# Main_PDU.net
KiCad netlist of a schematic drawn in EAGLE
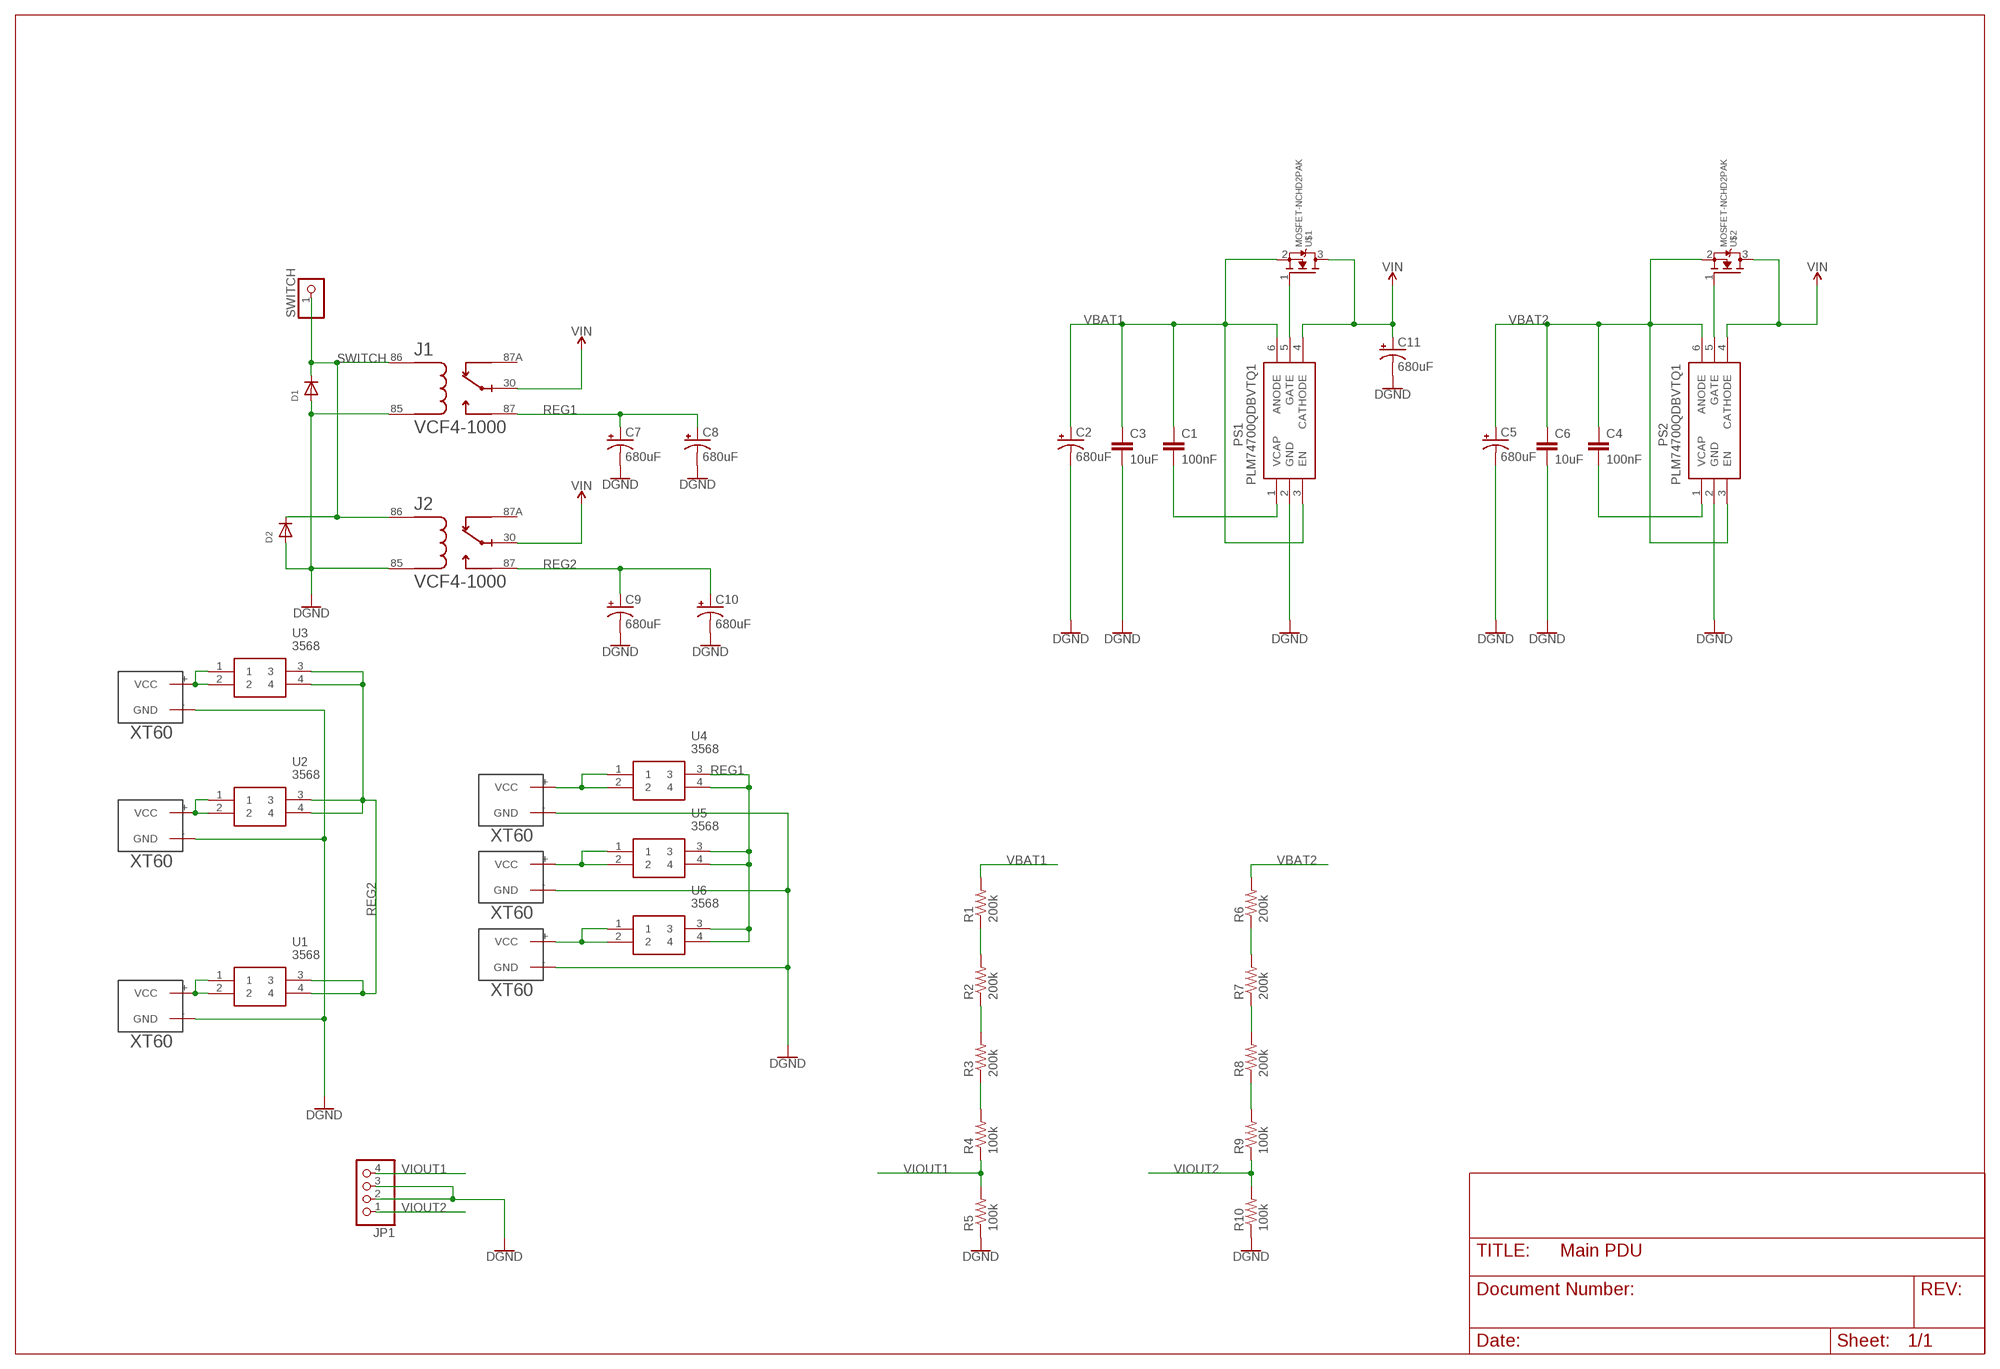
[diagram p0: schematic, sheet 1]

(export (version "E")
  (design (tool "Eeschema 10.0.6"))
  (components
    (comp (ref "C1")
      (value "100nF")
      (footprint "eagle-import:C0805")
      (libsource (lib "eagle-import") (part "C-EUC0805"))
    )
    (comp (ref "C2")
      (value "680uF")
      (footprint "eagle-import:E5-10,5")
      (libsource (lib "eagle-import") (part "CPOL-USE5-10.5"))
    )
    (comp (ref "C3")
      (value "10uF")
      (footprint "eagle-import:C1206")
      (libsource (lib "eagle-import") (part "C-EUC1206"))
    )
    (comp (ref "C4")
      (value "100nF")
      (footprint "eagle-import:C0805")
      (libsource (lib "eagle-import") (part "C-EUC0805"))
    )
    (comp (ref "C5")
      (value "680uF")
      (footprint "eagle-import:E5-10,5")
      (libsource (lib "eagle-import") (part "CPOL-USE5-10.5"))
    )
    (comp (ref "C6")
      (value "10uF")
      (footprint "eagle-import:C1206")
      (libsource (lib "eagle-import") (part "C-EUC1206"))
    )
    (comp (ref "C7")
      (value "680uF")
      (footprint "eagle-import:E5-10,5")
      (libsource (lib "eagle-import") (part "CPOL-USE5-10.5"))
    )
    (comp (ref "C8")
      (value "680uF")
      (footprint "eagle-import:E5-10,5")
      (libsource (lib "eagle-import") (part "CPOL-USE5-10.5"))
    )
    (comp (ref "C9")
      (value "680uF")
      (footprint "eagle-import:E5-10,5")
      (libsource (lib "eagle-import") (part "CPOL-USE5-10.5"))
    )
    (comp (ref "C10")
      (value "680uF")
      (footprint "eagle-import:E5-10,5")
      (libsource (lib "eagle-import") (part "CPOL-USE5-10.5"))
    )
    (comp (ref "C11")
      (value "680uF")
      (footprint "eagle-import:E5-10,5")
      (libsource (lib "eagle-import") (part "CPOL-USE5-10.5"))
    )
    (comp (ref "D1")
      (value "DIODESOD-123")
      (footprint "eagle-import:SOD-123")
      (libsource (lib "eagle-import") (part "DIODESOD-123"))
    )
    (comp (ref "D2")
      (value "DIODESOD-123")
      (footprint "eagle-import:SOD-123")
      (libsource (lib "eagle-import") (part "DIODESOD-123"))
    )
    (comp (ref "J1")
      (value "VCF4-1000")
      (footprint "eagle-import:TE_VCF4-1000")
      (fields (field (name "COMMENT") "1393310-3") (field (name "MF") "TE Connectivity"))
      (libsource (lib "eagle-import") (part "VCF4-1000"))
    )
    (comp (ref "J2")
      (value "VCF4-1000")
      (footprint "eagle-import:TE_VCF4-1000")
      (fields (field (name "COMMENT") "1393310-3") (field (name "MF") "TE Connectivity"))
      (libsource (lib "eagle-import") (part "VCF4-1000"))
    )
    (comp (ref "JP1")
      (value "PINHD-1X4")
      (footprint "eagle-import:1X04")
      (libsource (lib "eagle-import") (part "PINHD-1X4"))
    )
    (comp (ref "PS1")
      (value "PLM74700QDBVTQ1")
      (footprint "eagle-import:SOT95P280X145-6N")
      (fields (field (name "MOUSER_PART_NUMBER") "595-PLM74700QDBVTQ1"))
      (libsource (lib "eagle-import") (part "PLM74700QDBVTQ1"))
    )
    (comp (ref "PS2")
      (value "PLM74700QDBVTQ1")
      (footprint "eagle-import:SOT95P280X145-6N")
      (fields (field (name "MOUSER_PART_NUMBER") "595-PLM74700QDBVTQ1"))
      (libsource (lib "eagle-import") (part "PLM74700QDBVTQ1"))
    )
    (comp (ref "R1")
      (value "200k")
      (footprint "eagle-import:R0805")
      (libsource (lib "eagle-import") (part "R-US_R0805"))
    )
    (comp (ref "R2")
      (value "200k")
      (footprint "eagle-import:R0805")
      (libsource (lib "eagle-import") (part "R-US_R0805"))
    )
    (comp (ref "R3")
      (value "200k")
      (footprint "eagle-import:R0805")
      (libsource (lib "eagle-import") (part "R-US_R0805"))
    )
    (comp (ref "R4")
      (value "100k")
      (footprint "eagle-import:R0805")
      (libsource (lib "eagle-import") (part "R-US_R0805"))
    )
    (comp (ref "R5")
      (value "100k")
      (footprint "eagle-import:R0805")
      (libsource (lib "eagle-import") (part "R-US_R0805"))
    )
    (comp (ref "R6")
      (value "200k")
      (footprint "eagle-import:R0805")
      (libsource (lib "eagle-import") (part "R-US_R0805"))
    )
    (comp (ref "R7")
      (value "200k")
      (footprint "eagle-import:R0805")
      (libsource (lib "eagle-import") (part "R-US_R0805"))
    )
    (comp (ref "R8")
      (value "200k")
      (footprint "eagle-import:R0805")
      (libsource (lib "eagle-import") (part "R-US_R0805"))
    )
    (comp (ref "R9")
      (value "100k")
      (footprint "eagle-import:R0805")
      (libsource (lib "eagle-import") (part "R-US_R0805"))
    )
    (comp (ref "R10")
      (value "100k")
      (footprint "eagle-import:R0805")
      (libsource (lib "eagle-import") (part "R-US_R0805"))
    )
    (comp (ref "SWITCH")
      (value "PINHD-1X1")
      (footprint "eagle-import:1X01")
      (libsource (lib "eagle-import") (part "PINHD-1X1"))
    )
    (comp (ref "U$1")
      (value "MOSFET-NCHD2PAK")
      (footprint "eagle-import:MBRB41H100CTT4G")
      (libsource (lib "eagle-import") (part "MOSFET-NCHD2PAK"))
    )
    (comp (ref "U$2")
      (value "MOSFET-NCHD2PAK")
      (footprint "eagle-import:MBRB41H100CTT4G")
      (libsource (lib "eagle-import") (part "MOSFET-NCHD2PAK"))
    )
    (comp (ref "U$3")
      (value "XT60")
      (footprint "eagle-import:XT60")
      (libsource (lib "eagle-import") (part "XT60"))
    )
    (comp (ref "U$4")
      (value "XT60")
      (footprint "eagle-import:XT60")
      (libsource (lib "eagle-import") (part "XT60"))
    )
    (comp (ref "U$6")
      (value "XT60")
      (footprint "eagle-import:XT60")
      (libsource (lib "eagle-import") (part "XT60"))
    )
    (comp (ref "U$7")
      (value "XT60")
      (footprint "eagle-import:XT60")
      (libsource (lib "eagle-import") (part "XT60"))
    )
    (comp (ref "U$8")
      (value "XT60")
      (footprint "eagle-import:XT60")
      (libsource (lib "eagle-import") (part "XT60"))
    )
    (comp (ref "U$10")
      (value "XT60")
      (footprint "eagle-import:XT60")
      (libsource (lib "eagle-import") (part "XT60"))
    )
    (comp (ref "U1")
      (value "3568")
      (footprint "eagle-import:3568")
      (fields (field (name "MOUSER_PART_NUMBER") "534-3568"))
      (libsource (lib "eagle-import") (part "3568"))
    )
    (comp (ref "U2")
      (value "3568")
      (footprint "eagle-import:3568")
      (fields (field (name "MOUSER_PART_NUMBER") "534-3568"))
      (libsource (lib "eagle-import") (part "3568"))
    )
    (comp (ref "U3")
      (value "3568")
      (footprint "eagle-import:3568")
      (fields (field (name "MOUSER_PART_NUMBER") "534-3568"))
      (libsource (lib "eagle-import") (part "3568"))
    )
    (comp (ref "U4")
      (value "3568")
      (footprint "eagle-import:3568")
      (fields (field (name "MOUSER_PART_NUMBER") "534-3568"))
      (libsource (lib "eagle-import") (part "3568"))
    )
    (comp (ref "U5")
      (value "3568")
      (footprint "eagle-import:3568")
      (fields (field (name "MOUSER_PART_NUMBER") "534-3568"))
      (libsource (lib "eagle-import") (part "3568"))
    )
    (comp (ref "U6")
      (value "3568")
      (footprint "eagle-import:3568")
      (fields (field (name "MOUSER_PART_NUMBER") "534-3568"))
      (libsource (lib "eagle-import") (part "3568"))
    )
  )
  (nets
    (net (code "1") (name "/REG1") (class "Default")
      (node (ref "C7") (pin "+") (pinfunction "+_+") (pintype "passive"))
      (node (ref "C8") (pin "+") (pinfunction "+_+") (pintype "passive"))
      (node (ref "J1") (pin "87") (pinfunction "87_87") (pintype "passive"))
      (node (ref "U4") (pin "3") (pinfunction "3_3") (pintype "bidirectional"))
      (node (ref "U4") (pin "4") (pinfunction "4_4") (pintype "bidirectional"))
      (node (ref "U5") (pin "3") (pinfunction "3_3") (pintype "bidirectional"))
      (node (ref "U5") (pin "4") (pinfunction "4_4") (pintype "bidirectional"))
      (node (ref "U6") (pin "3") (pinfunction "3_3") (pintype "bidirectional"))
      (node (ref "U6") (pin "4") (pinfunction "4_4") (pintype "bidirectional"))
    )
    (net (code "2") (name "/REG2") (class "Default")
      (node (ref "C10") (pin "+") (pinfunction "+_+") (pintype "passive"))
      (node (ref "C9") (pin "+") (pinfunction "+_+") (pintype "passive"))
      (node (ref "J2") (pin "87") (pinfunction "87_87") (pintype "passive"))
      (node (ref "U1") (pin "3") (pinfunction "3_3") (pintype "bidirectional"))
      (node (ref "U1") (pin "4") (pinfunction "4_4") (pintype "bidirectional"))
      (node (ref "U2") (pin "3") (pinfunction "3_3") (pintype "bidirectional"))
      (node (ref "U2") (pin "4") (pinfunction "4_4") (pintype "bidirectional"))
      (node (ref "U3") (pin "3") (pinfunction "3_3") (pintype "bidirectional"))
      (node (ref "U3") (pin "4") (pinfunction "4_4") (pintype "bidirectional"))
    )
    (net (code "3") (name "/SWITCH") (class "Default")
      (node (ref "D1") (pin "C") (pinfunction "C_C") (pintype "passive"))
      (node (ref "D2") (pin "C") (pinfunction "C_C") (pintype "passive"))
      (node (ref "J1") (pin "86") (pinfunction "86_86") (pintype "passive"))
      (node (ref "J2") (pin "86") (pinfunction "86_86") (pintype "passive"))
      (node (ref "SWITCH") (pin "1") (pinfunction "1_1") (pintype "passive"))
    )
    (net (code "4") (name "/VBAT1") (class "Default")
      (node (ref "C1") (pin "1") (pinfunction "1_1") (pintype "passive"))
      (node (ref "C2") (pin "+") (pinfunction "+_+") (pintype "passive"))
      (node (ref "C3") (pin "1") (pinfunction "1_1") (pintype "passive"))
      (node (ref "PS1") (pin "3") (pinfunction "EN_3") (pintype "input"))
      (node (ref "PS1") (pin "6") (pinfunction "ANODE_6") (pintype "bidirectional"))
      (node (ref "R1") (pin "2") (pinfunction "2_2") (pintype "passive"))
      (node (ref "U$1") (pin "2") (pinfunction "S_2") (pintype "bidirectional"))
    )
    (net (code "5") (name "/VBAT2") (class "Default")
      (node (ref "C4") (pin "1") (pinfunction "1_1") (pintype "passive"))
      (node (ref "C5") (pin "+") (pinfunction "+_+") (pintype "passive"))
      (node (ref "C6") (pin "1") (pinfunction "1_1") (pintype "passive"))
      (node (ref "PS2") (pin "3") (pinfunction "EN_3") (pintype "input"))
      (node (ref "PS2") (pin "6") (pinfunction "ANODE_6") (pintype "bidirectional"))
      (node (ref "R6") (pin "2") (pinfunction "2_2") (pintype "passive"))
      (node (ref "U$2") (pin "2") (pinfunction "S_2") (pintype "bidirectional"))
    )
    (net (code "6") (name "/VIOUT1") (class "Default")
      (node (ref "JP1") (pin "4") (pinfunction "4_4") (pintype "passive"))
      (node (ref "R4") (pin "1") (pinfunction "1_1") (pintype "passive"))
      (node (ref "R5") (pin "2") (pinfunction "2_2") (pintype "passive"))
    )
    (net (code "7") (name "/VIOUT2") (class "Default")
      (node (ref "JP1") (pin "1") (pinfunction "1_1") (pintype "passive"))
      (node (ref "R10") (pin "2") (pinfunction "2_2") (pintype "passive"))
      (node (ref "R9") (pin "1") (pinfunction "1_1") (pintype "passive"))
    )
    (net (code "8") (name "DGND") (class "Default")
      (node (ref "C10") (pin "-") (pinfunction "-_-") (pintype "passive"))
      (node (ref "C11") (pin "-") (pinfunction "-_-") (pintype "passive"))
      (node (ref "C2") (pin "-") (pinfunction "-_-") (pintype "passive"))
      (node (ref "C3") (pin "2") (pinfunction "2_2") (pintype "passive"))
      (node (ref "C5") (pin "-") (pinfunction "-_-") (pintype "passive"))
      (node (ref "C6") (pin "2") (pinfunction "2_2") (pintype "passive"))
      (node (ref "C7") (pin "-") (pinfunction "-_-") (pintype "passive"))
      (node (ref "C8") (pin "-") (pinfunction "-_-") (pintype "passive"))
      (node (ref "C9") (pin "-") (pinfunction "-_-") (pintype "passive"))
      (node (ref "D1") (pin "A") (pinfunction "A_A") (pintype "passive"))
      (node (ref "D2") (pin "A") (pinfunction "A_A") (pintype "passive"))
      (node (ref "J1") (pin "85") (pinfunction "85_85") (pintype "passive"))
      (node (ref "J2") (pin "85") (pinfunction "85_85") (pintype "passive"))
      (node (ref "JP1") (pin "2") (pinfunction "2_2") (pintype "passive"))
      (node (ref "JP1") (pin "3") (pinfunction "3_3") (pintype "passive"))
      (node (ref "PS1") (pin "2") (pinfunction "GND_2") (pintype "power_in"))
      (node (ref "PS2") (pin "2") (pinfunction "GND_2") (pintype "power_in"))
      (node (ref "R10") (pin "1") (pinfunction "1_1") (pintype "passive"))
      (node (ref "R5") (pin "1") (pinfunction "1_1") (pintype "passive"))
      (node (ref "U$10") (pin "-") (pinfunction "GND_-") (pintype "bidirectional"))
      (node (ref "U$3") (pin "-") (pinfunction "GND_-") (pintype "bidirectional"))
      (node (ref "U$4") (pin "-") (pinfunction "GND_-") (pintype "bidirectional"))
      (node (ref "U$6") (pin "-") (pinfunction "GND_-") (pintype "bidirectional"))
      (node (ref "U$7") (pin "-") (pinfunction "GND_-") (pintype "bidirectional"))
      (node (ref "U$8") (pin "-") (pinfunction "GND_-") (pintype "bidirectional"))
    )
    (net (code "9") (name "Net-(PS1-GATE)") (class "Default")
      (node (ref "PS1") (pin "5") (pinfunction "GATE_5") (pintype "output"))
      (node (ref "U$1") (pin "1") (pinfunction "G_1") (pintype "bidirectional"))
    )
    (net (code "10") (name "Net-(PS1-VCAP)") (class "Default")
      (node (ref "C1") (pin "2") (pinfunction "2_2") (pintype "passive"))
      (node (ref "PS1") (pin "1") (pinfunction "VCAP_1") (pintype "bidirectional"))
    )
    (net (code "11") (name "Net-(PS2-GATE)") (class "Default")
      (node (ref "PS2") (pin "5") (pinfunction "GATE_5") (pintype "output"))
      (node (ref "U$2") (pin "1") (pinfunction "G_1") (pintype "bidirectional"))
    )
    (net (code "12") (name "Net-(PS2-VCAP)") (class "Default")
      (node (ref "C4") (pin "2") (pinfunction "2_2") (pintype "passive"))
      (node (ref "PS2") (pin "1") (pinfunction "VCAP_1") (pintype "bidirectional"))
    )
    (net (code "13") (name "Net-(R1-Pad1)") (class "Default")
      (node (ref "R1") (pin "1") (pinfunction "1_1") (pintype "passive"))
      (node (ref "R2") (pin "2") (pinfunction "2_2") (pintype "passive"))
    )
    (net (code "14") (name "Net-(R2-Pad1)") (class "Default")
      (node (ref "R2") (pin "1") (pinfunction "1_1") (pintype "passive"))
      (node (ref "R3") (pin "2") (pinfunction "2_2") (pintype "passive"))
    )
    (net (code "15") (name "Net-(R3-Pad1)") (class "Default")
      (node (ref "R3") (pin "1") (pinfunction "1_1") (pintype "passive"))
      (node (ref "R4") (pin "2") (pinfunction "2_2") (pintype "passive"))
    )
    (net (code "16") (name "Net-(R6-Pad1)") (class "Default")
      (node (ref "R6") (pin "1") (pinfunction "1_1") (pintype "passive"))
      (node (ref "R7") (pin "2") (pinfunction "2_2") (pintype "passive"))
    )
    (net (code "17") (name "Net-(R7-Pad1)") (class "Default")
      (node (ref "R7") (pin "1") (pinfunction "1_1") (pintype "passive"))
      (node (ref "R8") (pin "2") (pinfunction "2_2") (pintype "passive"))
    )
    (net (code "18") (name "Net-(R8-Pad1)") (class "Default")
      (node (ref "R8") (pin "1") (pinfunction "1_1") (pintype "passive"))
      (node (ref "R9") (pin "2") (pinfunction "2_2") (pintype "passive"))
    )
    (net (code "19") (name "Net-(U$3-VCC)") (class "Default")
      (node (ref "U$3") (pin "+") (pinfunction "VCC_+") (pintype "bidirectional"))
      (node (ref "U5") (pin "1") (pinfunction "1_1") (pintype "bidirectional"))
      (node (ref "U5") (pin "2") (pinfunction "2_2") (pintype "bidirectional"))
    )
    (net (code "20") (name "Net-(U$4-VCC)") (class "Default")
      (node (ref "U$4") (pin "+") (pinfunction "VCC_+") (pintype "bidirectional"))
      (node (ref "U6") (pin "1") (pinfunction "1_1") (pintype "bidirectional"))
      (node (ref "U6") (pin "2") (pinfunction "2_2") (pintype "bidirectional"))
    )
    (net (code "21") (name "Net-(U$6-VCC)") (class "Default")
      (node (ref "U$6") (pin "+") (pinfunction "VCC_+") (pintype "bidirectional"))
      (node (ref "U4") (pin "1") (pinfunction "1_1") (pintype "bidirectional"))
      (node (ref "U4") (pin "2") (pinfunction "2_2") (pintype "bidirectional"))
    )
    (net (code "22") (name "Net-(U$7-VCC)") (class "Default")
      (node (ref "U$7") (pin "+") (pinfunction "VCC_+") (pintype "bidirectional"))
      (node (ref "U2") (pin "1") (pinfunction "1_1") (pintype "bidirectional"))
      (node (ref "U2") (pin "2") (pinfunction "2_2") (pintype "bidirectional"))
    )
    (net (code "23") (name "Net-(U$8-VCC)") (class "Default")
      (node (ref "U$8") (pin "+") (pinfunction "VCC_+") (pintype "bidirectional"))
      (node (ref "U1") (pin "1") (pinfunction "1_1") (pintype "bidirectional"))
      (node (ref "U1") (pin "2") (pinfunction "2_2") (pintype "bidirectional"))
    )
    (net (code "24") (name "Net-(U$10-VCC)") (class "Default")
      (node (ref "U$10") (pin "+") (pinfunction "VCC_+") (pintype "bidirectional"))
      (node (ref "U3") (pin "1") (pinfunction "1_1") (pintype "bidirectional"))
      (node (ref "U3") (pin "2") (pinfunction "2_2") (pintype "bidirectional"))
    )
    (net (code "25") (name "VIN") (class "Default")
      (node (ref "C11") (pin "+") (pinfunction "+_+") (pintype "passive"))
      (node (ref "J1") (pin "30") (pinfunction "30_30") (pintype "passive"))
      (node (ref "J2") (pin "30") (pinfunction "30_30") (pintype "passive"))
      (node (ref "PS1") (pin "4") (pinfunction "CATHODE_4") (pintype "bidirectional"))
      (node (ref "PS2") (pin "4") (pinfunction "CATHODE_4") (pintype "bidirectional"))
      (node (ref "U$1") (pin "3") (pinfunction "D_3") (pintype "bidirectional"))
      (node (ref "U$2") (pin "3") (pinfunction "D_3") (pintype "bidirectional"))
    )
    (net (code "26") (name "unconnected-(J1-Pad87A)") (class "Default")
      (node (ref "J1") (pin "87A") (pinfunction "87A_87A") (pintype "passive"))
    )
    (net (code "27") (name "unconnected-(J2-Pad87A)") (class "Default")
      (node (ref "J2") (pin "87A") (pinfunction "87A_87A") (pintype "passive"))
    )
  )
)
